# Emetteur2_2.net
KiCad netlist of a schematic drawn in EAGLE
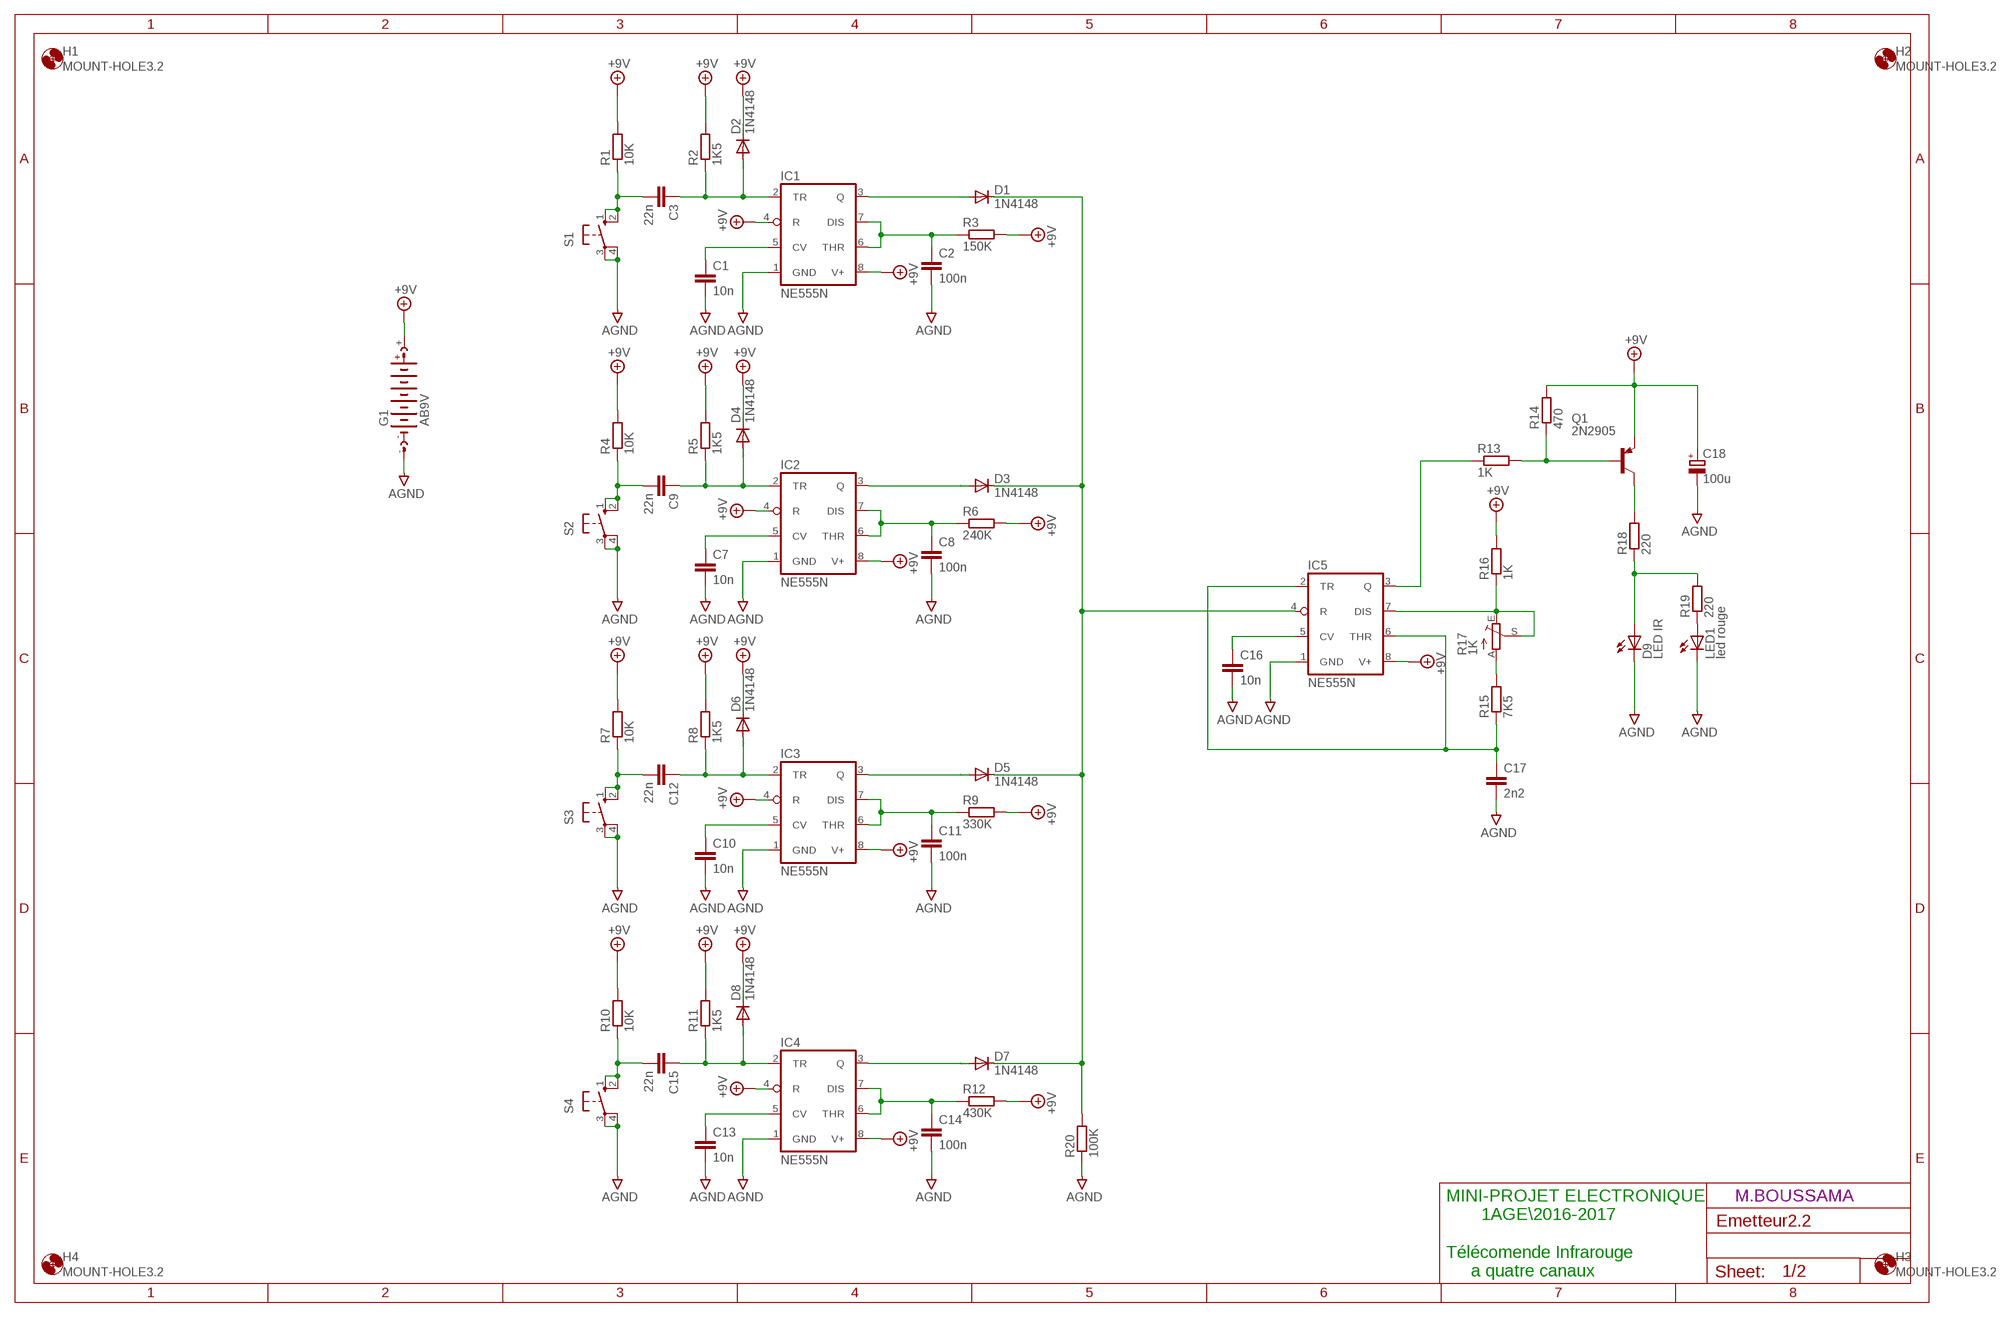
[diagram p0: schematic, sheet 1]
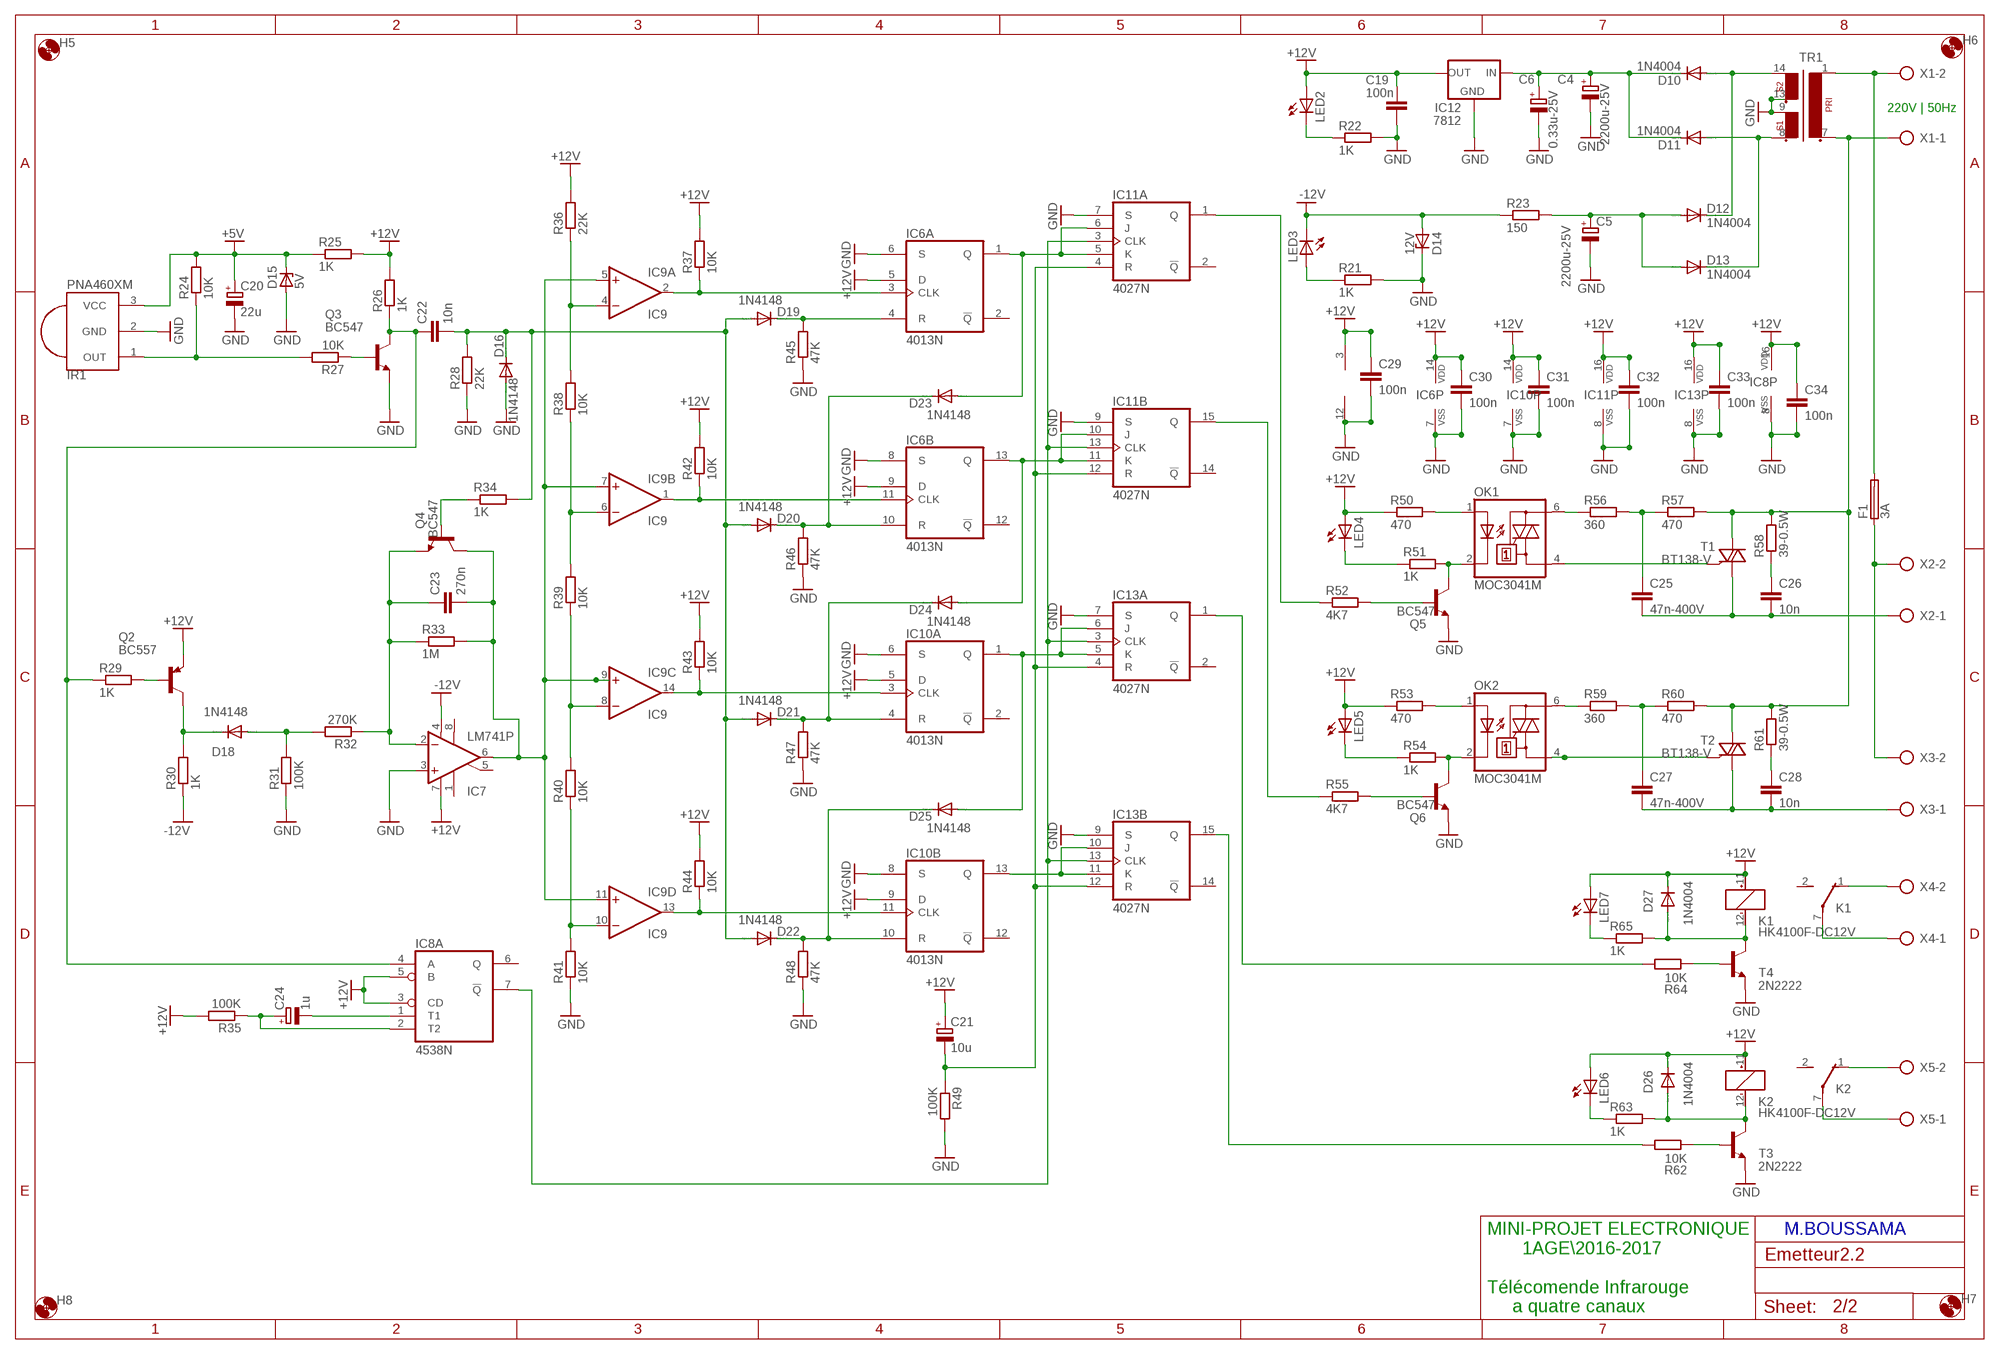
[diagram p1: schematic, sheet 2]

(export (version "E")
  (design (tool "Eeschema 10.0.6"))
  (components
    (comp (ref "C4")
      (value "2200u-25V")
      (footprint "eagle-import:E5-13")
      (libsource (lib "eagle-import") (part "CPOL-EUE5-13"))
    )
    (comp (ref "C5")
      (value "2200u-25V")
      (footprint "eagle-import:E5-13")
      (libsource (lib "eagle-import") (part "CPOL-EUE5-13"))
    )
    (comp (ref "C6")
      (value "0.33u-25V")
      (footprint "eagle-import:E5-5")
      (libsource (lib "eagle-import") (part "CPOL-EUE5-5"))
    )
    (comp (ref "C19")
      (value "100n")
      (footprint "eagle-import:C050-025X075")
      (libsource (lib "eagle-import") (part "C-EU050-025X075"))
    )
    (comp (ref "C20")
      (value "22u")
      (footprint "eagle-import:E2,5-6")
      (libsource (lib "eagle-import") (part "CPOL-EUE2.5-6"))
    )
    (comp (ref "C21")
      (value "10u")
      (footprint "eagle-import:E2,5-6E")
      (libsource (lib "eagle-import") (part "CPOL-EUE2,5-6E"))
    )
    (comp (ref "C22")
      (value "10n")
      (footprint "eagle-import:C050-025X075")
      (libsource (lib "eagle-import") (part "C-EU050-025X075"))
    )
    (comp (ref "C23")
      (value "270n")
      (footprint "eagle-import:C050-035X075")
      (libsource (lib "eagle-import") (part "C-EU050-035X075"))
    )
    (comp (ref "C24")
      (value "1u")
      (footprint "eagle-import:E2,5-6E")
      (libsource (lib "eagle-import") (part "CPOL-EUE2,5-6E"))
    )
    (comp (ref "C25")
      (value "47n-400V")
      (footprint "eagle-import:C150-054X183")
      (libsource (lib "eagle-import") (part "C-EU150-054X183"))
    )
    (comp (ref "C26")
      (value "10n")
      (footprint "eagle-import:C102-043X133")
      (libsource (lib "eagle-import") (part "C-EU102-043X133"))
    )
    (comp (ref "C27")
      (value "47n-400V")
      (footprint "eagle-import:C150-054X183")
      (libsource (lib "eagle-import") (part "C-EU150-054X183"))
    )
    (comp (ref "C28")
      (value "10n")
      (footprint "eagle-import:C102-043X133")
      (libsource (lib "eagle-import") (part "C-EU102-043X133"))
    )
    (comp (ref "C29")
      (value "100n")
      (footprint "eagle-import:C050-025X075")
      (libsource (lib "eagle-import") (part "C-EU050-025X075"))
    )
    (comp (ref "C30")
      (value "100n")
      (footprint "eagle-import:C050-025X075")
      (libsource (lib "eagle-import") (part "C-EU050-025X075"))
    )
    (comp (ref "C31")
      (value "100n")
      (footprint "eagle-import:C050-025X075")
      (libsource (lib "eagle-import") (part "C-EU050-025X075"))
    )
    (comp (ref "C32")
      (value "100n")
      (footprint "eagle-import:C050-025X075")
      (libsource (lib "eagle-import") (part "C-EU050-025X075"))
    )
    (comp (ref "C33")
      (value "100n")
      (footprint "eagle-import:C050-025X075")
      (libsource (lib "eagle-import") (part "C-EU050-025X075"))
    )
    (comp (ref "C34")
      (value "100n")
      (footprint "eagle-import:C050-025X075")
      (libsource (lib "eagle-import") (part "C-EU050-025X075"))
    )
    (comp (ref "D10")
      (value "1N4004")
      (footprint "eagle-import:DO41-10")
      (libsource (lib "eagle-import") (part "1N4004"))
    )
    (comp (ref "D11")
      (value "1N4004")
      (footprint "eagle-import:DO41-10")
      (libsource (lib "eagle-import") (part "1N4004"))
    )
    (comp (ref "D12")
      (value "1N4004")
      (footprint "eagle-import:DO41-10")
      (libsource (lib "eagle-import") (part "1N4004"))
    )
    (comp (ref "D13")
      (value "1N4004")
      (footprint "eagle-import:DO41-10")
      (libsource (lib "eagle-import") (part "1N4004"))
    )
    (comp (ref "D14")
      (value "12V")
      (footprint "eagle-import:DO41Z10")
      (libsource (lib "eagle-import") (part "1N4728"))
    )
    (comp (ref "D15")
      (value "5V")
      (footprint "eagle-import:DO41Z10")
      (libsource (lib "eagle-import") (part "1N4728"))
    )
    (comp (ref "D16")
      (value "1N4148")
      (footprint "eagle-import:DO35-10")
      (libsource (lib "eagle-import") (part "1N4148DO35-10"))
    )
    (comp (ref "D18")
      (value "1N4148")
      (footprint "eagle-import:DO35-7")
      (libsource (lib "eagle-import") (part "1N4148DO35-7"))
    )
    (comp (ref "D19")
      (value "1N4148")
      (footprint "eagle-import:DO35-10")
      (libsource (lib "eagle-import") (part "1N4148DO35-10"))
    )
    (comp (ref "D20")
      (value "1N4148")
      (footprint "eagle-import:SOD61B")
      (libsource (lib "eagle-import") (part "BY609"))
    )
    (comp (ref "D21")
      (value "1N4148")
      (footprint "eagle-import:DO35-10")
      (libsource (lib "eagle-import") (part "1N4148DO35-10"))
    )
    (comp (ref "D22")
      (value "1N4148")
      (footprint "eagle-import:SOD61B")
      (libsource (lib "eagle-import") (part "BY609"))
    )
    (comp (ref "D23")
      (value "1N4148")
      (footprint "eagle-import:DO35-10")
      (libsource (lib "eagle-import") (part "1N4148DO35-10"))
    )
    (comp (ref "D24")
      (value "1N4148")
      (footprint "eagle-import:SOD61B")
      (libsource (lib "eagle-import") (part "BY609"))
    )
    (comp (ref "D25")
      (value "1N4148")
      (footprint "eagle-import:DO35-10")
      (libsource (lib "eagle-import") (part "1N4148DO35-10"))
    )
    (comp (ref "D26")
      (value "1N4004")
      (footprint "eagle-import:DO41-10")
      (libsource (lib "eagle-import") (part "1N4004"))
    )
    (comp (ref "D27")
      (value "1N4004")
      (footprint "eagle-import:DO41-10")
      (libsource (lib "eagle-import") (part "1N4004"))
    )
    (comp (ref "F1")
      (value "3A")
      (footprint "eagle-import:GSH15")
      (libsource (lib "eagle-import") (part "FUSEGSH15"))
    )
    (comp (ref "H5")
      (value "MOUNT-HOLE3.2")
      (footprint "eagle-import:3,2")
      (libsource (lib "eagle-import") (part "MOUNT-HOLE3.2"))
    )
    (comp (ref "H6")
      (value "MOUNT-HOLE3.2")
      (footprint "eagle-import:3,2")
      (libsource (lib "eagle-import") (part "MOUNT-HOLE3.2"))
    )
    (comp (ref "H7")
      (value "MOUNT-HOLE3.2")
      (footprint "eagle-import:3,2")
      (libsource (lib "eagle-import") (part "MOUNT-HOLE3.2"))
    )
    (comp (ref "H8")
      (value "MOUNT-HOLE3.2")
      (footprint "eagle-import:3,2")
      (libsource (lib "eagle-import") (part "MOUNT-HOLE3.2"))
    )
    (comp (ref "IC6")
      (value "4013N")
      (footprint "eagle-import:DIL14")
      (libsource (lib "eagle-import") (part "4013N"))
    )
    (comp (ref "IC7")
      (value "LM741P")
      (footprint "eagle-import:DIL08")
      (libsource (lib "eagle-import") (part "741PLM"))
    )
    (comp (ref "IC8")
      (value "4538N")
      (footprint "eagle-import:DIL16")
      (libsource (lib "eagle-import") (part "4538N"))
    )
    (comp (ref "IC9")
      (value "IC9")
      (footprint "eagle-import:DIL14")
      (libsource (lib "eagle-import") (part "LM339N"))
    )
    (comp (ref "IC10")
      (value "4013N")
      (footprint "eagle-import:DIL14")
      (libsource (lib "eagle-import") (part "4013N"))
    )
    (comp (ref "IC11")
      (value "4027N")
      (footprint "eagle-import:DIL16")
      (libsource (lib "eagle-import") (part "4027N"))
    )
    (comp (ref "IC12")
      (value "7812")
      (footprint "eagle-import:78XXS")
      (libsource (lib "eagle-import") (part "78XXS"))
    )
    (comp (ref "IC13")
      (value "4027N")
      (footprint "eagle-import:DIL16")
      (libsource (lib "eagle-import") (part "4027N"))
    )
    (comp (ref "IR1")
      (value "PNA460XM")
      (footprint "eagle-import:PNA460XM")
      (libsource (lib "eagle-import") (part "PNA460XM"))
    )
    (comp (ref "K1")
      (value "HK4100F-DC12V")
      (footprint "eagle-import:SMR1")
      (libsource (lib "eagle-import") (part "HK410?F-0DC12V"))
    )
    (comp (ref "K2")
      (value "HK4100F-DC12V")
      (footprint "eagle-import:SMR1")
      (libsource (lib "eagle-import") (part "HK410?F-0DC12V"))
    )
    (comp (ref "LED2")
      (value "LED3MM")
      (footprint "eagle-import:LED3MM")
      (libsource (lib "eagle-import") (part "LED3MM"))
    )
    (comp (ref "LED3")
      (value "LED3MM")
      (footprint "eagle-import:LED3MM")
      (libsource (lib "eagle-import") (part "LED3MM"))
    )
    (comp (ref "LED4")
      (value "LED3MM")
      (footprint "eagle-import:LED3MM")
      (libsource (lib "eagle-import") (part "LED3MM"))
    )
    (comp (ref "LED5")
      (value "LED3MM")
      (footprint "eagle-import:LED3MM")
      (libsource (lib "eagle-import") (part "LED3MM"))
    )
    (comp (ref "LED6")
      (value "LED3MM")
      (footprint "eagle-import:LED3MM")
      (libsource (lib "eagle-import") (part "LED3MM"))
    )
    (comp (ref "LED7")
      (value "LED3MM")
      (footprint "eagle-import:LED3MM")
      (libsource (lib "eagle-import") (part "LED3MM"))
    )
    (comp (ref "OK1")
      (value "MOC3041M")
      (footprint "eagle-import:DIL06")
      (fields (field (name "MF") "FAIRCHILD SEMICONDUCTOR"))
      (libsource (lib "eagle-import") (part "MOC3041M"))
    )
    (comp (ref "OK2")
      (value "MOC3041M")
      (footprint "eagle-import:DIL06")
      (fields (field (name "MF") "FAIRCHILD SEMICONDUCTOR"))
      (libsource (lib "eagle-import") (part "MOC3041M"))
    )
    (comp (ref "Q2")
      (value "BC557")
      (footprint "eagle-import:TO92-EBC")
      (libsource (lib "eagle-import") (part "BC557"))
    )
    (comp (ref "Q3")
      (value "BC547")
      (footprint "eagle-import:TO92-EBC")
      (libsource (lib "eagle-import") (part "BC548"))
    )
    (comp (ref "Q4")
      (value "BC547")
      (footprint "eagle-import:TO92-EBC")
      (libsource (lib "eagle-import") (part "BC548"))
    )
    (comp (ref "Q5")
      (value "BC547")
      (footprint "eagle-import:TO92-EBC")
      (libsource (lib "eagle-import") (part "BC548"))
    )
    (comp (ref "Q6")
      (value "BC547")
      (footprint "eagle-import:TO92-EBC")
      (libsource (lib "eagle-import") (part "BC548"))
    )
    (comp (ref "R21")
      (value "1K")
      (footprint "eagle-import:0207_10")
      (libsource (lib "eagle-import") (part "R-EU_0207/10"))
    )
    (comp (ref "R22")
      (value "1K")
      (footprint "eagle-import:0207_10")
      (libsource (lib "eagle-import") (part "R-EU_0207/10"))
    )
    (comp (ref "R23")
      (value "150")
      (footprint "eagle-import:0207_10")
      (libsource (lib "eagle-import") (part "R-EU_0207/10"))
    )
    (comp (ref "R24")
      (value "10K")
      (footprint "eagle-import:0207_10")
      (libsource (lib "eagle-import") (part "R-EU_0207/10"))
    )
    (comp (ref "R25")
      (value "1K")
      (footprint "eagle-import:0207_10")
      (libsource (lib "eagle-import") (part "R-EU_0207/10"))
    )
    (comp (ref "R26")
      (value "1K")
      (footprint "eagle-import:0207_12")
      (libsource (lib "eagle-import") (part "R-EU_0207/12"))
    )
    (comp (ref "R27")
      (value "10K")
      (footprint "eagle-import:0207_10")
      (libsource (lib "eagle-import") (part "R-EU_0207/10"))
    )
    (comp (ref "R28")
      (value "22K")
      (footprint "eagle-import:0207_10")
      (libsource (lib "eagle-import") (part "R-EU_0207/10"))
    )
    (comp (ref "R29")
      (value "1K")
      (footprint "eagle-import:0207_15")
      (libsource (lib "eagle-import") (part "R-EU_0207/15"))
    )
    (comp (ref "R30")
      (value "1K")
      (footprint "eagle-import:0207_10")
      (libsource (lib "eagle-import") (part "R-EU_0207/10"))
    )
    (comp (ref "R31")
      (value "100K")
      (footprint "eagle-import:0207_10")
      (libsource (lib "eagle-import") (part "R-EU_0207/10"))
    )
    (comp (ref "R32")
      (value "270K")
      (footprint "eagle-import:0207_12")
      (libsource (lib "eagle-import") (part "R-EU_0207/12"))
    )
    (comp (ref "R33")
      (value "1M")
      (footprint "eagle-import:0207_10")
      (libsource (lib "eagle-import") (part "R-EU_0207/10"))
    )
    (comp (ref "R34")
      (value "1K")
      (footprint "eagle-import:0207_12")
      (libsource (lib "eagle-import") (part "R-EU_0207/12"))
    )
    (comp (ref "R35")
      (value "100K")
      (footprint "eagle-import:0207_10")
      (libsource (lib "eagle-import") (part "R-EU_0207/10"))
    )
    (comp (ref "R36")
      (value "22K")
      (footprint "eagle-import:0207_10")
      (libsource (lib "eagle-import") (part "R-EU_0207/10"))
    )
    (comp (ref "R37")
      (value "10K")
      (footprint "eagle-import:0207_10")
      (libsource (lib "eagle-import") (part "R-EU_0207/10"))
    )
    (comp (ref "R38")
      (value "10K")
      (footprint "eagle-import:0207_10")
      (libsource (lib "eagle-import") (part "R-EU_0207/10"))
    )
    (comp (ref "R39")
      (value "10K")
      (footprint "eagle-import:0207_10")
      (libsource (lib "eagle-import") (part "R-EU_0207/10"))
    )
    (comp (ref "R40")
      (value "10K")
      (footprint "eagle-import:0207_10")
      (libsource (lib "eagle-import") (part "R-EU_0207/10"))
    )
    (comp (ref "R41")
      (value "10K")
      (footprint "eagle-import:0207_10")
      (libsource (lib "eagle-import") (part "R-EU_0207/10"))
    )
    (comp (ref "R42")
      (value "10K")
      (footprint "eagle-import:0207_10")
      (libsource (lib "eagle-import") (part "R-EU_0207/10"))
    )
    (comp (ref "R43")
      (value "10K")
      (footprint "eagle-import:0207_10")
      (libsource (lib "eagle-import") (part "R-EU_0207/10"))
    )
    (comp (ref "R44")
      (value "10K")
      (footprint "eagle-import:0207_10")
      (libsource (lib "eagle-import") (part "R-EU_0207/10"))
    )
    (comp (ref "R45")
      (value "47K")
      (footprint "eagle-import:0207_12")
      (libsource (lib "eagle-import") (part "R-EU_0207/12"))
    )
    (comp (ref "R46")
      (value "47K")
      (footprint "eagle-import:0207_12")
      (libsource (lib "eagle-import") (part "R-EU_0207/12"))
    )
    (comp (ref "R47")
      (value "47K")
      (footprint "eagle-import:0207_12")
      (libsource (lib "eagle-import") (part "R-EU_0207/12"))
    )
    (comp (ref "R48")
      (value "47K")
      (footprint "eagle-import:0207_10")
      (libsource (lib "eagle-import") (part "R-EU_0207/10"))
    )
    (comp (ref "R49")
      (value "100K")
      (footprint "eagle-import:0207_12")
      (libsource (lib "eagle-import") (part "R-EU_0207/12"))
    )
    (comp (ref "R50")
      (value "470")
      (footprint "eagle-import:0207_10")
      (libsource (lib "eagle-import") (part "R-EU_0207/10"))
    )
    (comp (ref "R51")
      (value "1K")
      (footprint "eagle-import:0207_10")
      (libsource (lib "eagle-import") (part "R-EU_0207/10"))
    )
    (comp (ref "R52")
      (value "4K7")
      (footprint "eagle-import:0207_10")
      (libsource (lib "eagle-import") (part "R-EU_0207/10"))
    )
    (comp (ref "R53")
      (value "470")
      (footprint "eagle-import:0207_10")
      (libsource (lib "eagle-import") (part "R-EU_0207/10"))
    )
    (comp (ref "R54")
      (value "1K")
      (footprint "eagle-import:0207_10")
      (libsource (lib "eagle-import") (part "R-EU_0207/10"))
    )
    (comp (ref "R55")
      (value "4K7")
      (footprint "eagle-import:0207_10")
      (libsource (lib "eagle-import") (part "R-EU_0207/10"))
    )
    (comp (ref "R56")
      (value "360")
      (footprint "eagle-import:0207_10")
      (libsource (lib "eagle-import") (part "R-EU_0207/10"))
    )
    (comp (ref "R57")
      (value "470")
      (footprint "eagle-import:0207_10")
      (libsource (lib "eagle-import") (part "R-EU_0207/10"))
    )
    (comp (ref "R58")
      (value "39-0.5W")
      (footprint "eagle-import:0207_10")
      (libsource (lib "eagle-import") (part "R-EU_0207/10"))
    )
    (comp (ref "R59")
      (value "360")
      (footprint "eagle-import:0207_10")
      (libsource (lib "eagle-import") (part "R-EU_0207/10"))
    )
    (comp (ref "R60")
      (value "470")
      (footprint "eagle-import:0207_10")
      (libsource (lib "eagle-import") (part "R-EU_0207/10"))
    )
    (comp (ref "R61")
      (value "39-0.5W")
      (footprint "eagle-import:0207_10")
      (libsource (lib "eagle-import") (part "R-EU_0207/10"))
    )
    (comp (ref "R62")
      (value "10K")
      (footprint "eagle-import:0207_12")
      (libsource (lib "eagle-import") (part "R-EU_0207/12"))
    )
    (comp (ref "R63")
      (value "1K")
      (footprint "eagle-import:0207_10")
      (libsource (lib "eagle-import") (part "R-EU_0207/10"))
    )
    (comp (ref "R64")
      (value "10K")
      (footprint "eagle-import:0207_12")
      (libsource (lib "eagle-import") (part "R-EU_0207/12"))
    )
    (comp (ref "R65")
      (value "1K")
      (footprint "eagle-import:0207_10")
      (libsource (lib "eagle-import") (part "R-EU_0207/10"))
    )
    (comp (ref "T1")
      (value "BT138-V")
      (footprint "eagle-import:TO220BV")
      (libsource (lib "eagle-import") (part "BT138-V"))
    )
    (comp (ref "T2")
      (value "BT138-V")
      (footprint "eagle-import:TO220BV")
      (libsource (lib "eagle-import") (part "BT138-V"))
    )
    (comp (ref "T3")
      (value "2N2222")
      (footprint "eagle-import:TO92-EBC-OVAL")
      (libsource (lib "eagle-import") (part "2N2222"))
    )
    (comp (ref "T4")
      (value "2N2222")
      (footprint "eagle-import:TO92-EBC-OVAL")
      (libsource (lib "eagle-import") (part "2N2222"))
    )
    (comp (ref "TR1")
      (value "EI54-2")
      (footprint "eagle-import:EI54-2")
      (libsource (lib "eagle-import") (part "EI54-2"))
    )
    (comp (ref "X1")
      (value "AK300/2")
      (footprint "eagle-import:AK300_2")
      (libsource (lib "eagle-import") (part "AK300/2"))
    )
    (comp (ref "X2")
      (value "AK300/2")
      (footprint "eagle-import:AK300_2")
      (libsource (lib "eagle-import") (part "AK300/2"))
    )
    (comp (ref "X3")
      (value "AK300/2")
      (footprint "eagle-import:AK300_2")
      (libsource (lib "eagle-import") (part "AK300/2"))
    )
    (comp (ref "X4")
      (value "AK300/2")
      (footprint "eagle-import:AK300_2")
      (libsource (lib "eagle-import") (part "AK300/2"))
    )
    (comp (ref "X5")
      (value "AK300/2")
      (footprint "eagle-import:AK300_2")
      (libsource (lib "eagle-import") (part "AK300/2"))
    )
    (comp (ref "C1")
      (value "10n")
      (footprint "eagle-import:C050-025X075")
      (libsource (lib "eagle-import") (part "C-EU050-025X075"))
    )
    (comp (ref "C2")
      (value "100n")
      (footprint "eagle-import:C050-030X075")
      (libsource (lib "eagle-import") (part "C-EU050-030X075"))
    )
    (comp (ref "C3")
      (value "22n")
      (footprint "eagle-import:C050-025X075")
      (libsource (lib "eagle-import") (part "C-EU050-025X075"))
    )
    (comp (ref "C7")
      (value "10n")
      (footprint "eagle-import:C050-025X075")
      (libsource (lib "eagle-import") (part "C-EU050-025X075"))
    )
    (comp (ref "C8")
      (value "100n")
      (footprint "eagle-import:C050-030X075")
      (libsource (lib "eagle-import") (part "C-EU050-030X075"))
    )
    (comp (ref "C9")
      (value "22n")
      (footprint "eagle-import:C050-025X075")
      (libsource (lib "eagle-import") (part "C-EU050-025X075"))
    )
    (comp (ref "C10")
      (value "10n")
      (footprint "eagle-import:C050-025X075")
      (libsource (lib "eagle-import") (part "C-EU050-025X075"))
    )
    (comp (ref "C11")
      (value "100n")
      (footprint "eagle-import:C050-030X075")
      (libsource (lib "eagle-import") (part "C-EU050-030X075"))
    )
    (comp (ref "C12")
      (value "22n")
      (footprint "eagle-import:C050-025X075")
      (libsource (lib "eagle-import") (part "C-EU050-025X075"))
    )
    (comp (ref "C13")
      (value "10n")
      (footprint "eagle-import:C050-025X075")
      (libsource (lib "eagle-import") (part "C-EU050-025X075"))
    )
    (comp (ref "C14")
      (value "100n")
      (footprint "eagle-import:C050-030X075")
      (libsource (lib "eagle-import") (part "C-EU050-030X075"))
    )
    (comp (ref "C15")
      (value "22n")
      (footprint "eagle-import:C050-025X075")
      (libsource (lib "eagle-import") (part "C-EU050-025X075"))
    )
    (comp (ref "C16")
      (value "10n")
      (footprint "eagle-import:C050-025X075")
      (libsource (lib "eagle-import") (part "C-EU050-025X075"))
    )
    (comp (ref "C17")
      (value "2n2")
      (footprint "eagle-import:C050-025X075")
      (libsource (lib "eagle-import") (part "C-EU050-025X075"))
    )
    (comp (ref "C18")
      (value "100u")
      (footprint "eagle-import:E5-4")
      (libsource (lib "eagle-import") (part "CPOL-EUE5-4"))
    )
    (comp (ref "D1")
      (value "1N4148")
      (footprint "eagle-import:DO35-7")
      (libsource (lib "eagle-import") (part "1N4148DO35-7"))
    )
    (comp (ref "D2")
      (value "1N4148")
      (footprint "eagle-import:DO35-7")
      (libsource (lib "eagle-import") (part "1N4148DO35-7"))
    )
    (comp (ref "D3")
      (value "1N4148")
      (footprint "eagle-import:DO35-7")
      (libsource (lib "eagle-import") (part "1N4148DO35-7"))
    )
    (comp (ref "D4")
      (value "1N4148")
      (footprint "eagle-import:DO35-7")
      (libsource (lib "eagle-import") (part "1N4148DO35-7"))
    )
    (comp (ref "D5")
      (value "1N4148")
      (footprint "eagle-import:DO35-7")
      (libsource (lib "eagle-import") (part "1N4148DO35-7"))
    )
    (comp (ref "D6")
      (value "1N4148")
      (footprint "eagle-import:DO35-7")
      (libsource (lib "eagle-import") (part "1N4148DO35-7"))
    )
    (comp (ref "D7")
      (value "1N4148")
      (footprint "eagle-import:DO35-7")
      (libsource (lib "eagle-import") (part "1N4148DO35-7"))
    )
    (comp (ref "D8")
      (value "1N4148")
      (footprint "eagle-import:DO35-7")
      (libsource (lib "eagle-import") (part "1N4148DO35-7"))
    )
    (comp (ref "D9")
      (value "LED IR")
      (footprint "eagle-import:SFH482")
      (libsource (lib "eagle-import") (part "SFH482"))
    )
    (comp (ref "G1")
      (value "AB9V")
      (footprint "eagle-import:AB9V")
      (libsource (lib "eagle-import") (part "AB9V"))
    )
    (comp (ref "H1")
      (value "MOUNT-HOLE3.2")
      (footprint "eagle-import:3,2")
      (libsource (lib "eagle-import") (part "MOUNT-HOLE3.2"))
    )
    (comp (ref "H2")
      (value "MOUNT-HOLE3.2")
      (footprint "eagle-import:3,2")
      (libsource (lib "eagle-import") (part "MOUNT-HOLE3.2"))
    )
    (comp (ref "H3")
      (value "MOUNT-HOLE3.2")
      (footprint "eagle-import:3,2")
      (libsource (lib "eagle-import") (part "MOUNT-HOLE3.2"))
    )
    (comp (ref "H4")
      (value "MOUNT-HOLE3.2")
      (footprint "eagle-import:3,2")
      (libsource (lib "eagle-import") (part "MOUNT-HOLE3.2"))
    )
    (comp (ref "IC1")
      (value "NE555N")
      (footprint "eagle-import:DIL08")
      (libsource (lib "eagle-import") (part "555NNE"))
    )
    (comp (ref "IC2")
      (value "NE555N")
      (footprint "eagle-import:DIL08")
      (libsource (lib "eagle-import") (part "555NNE"))
    )
    (comp (ref "IC3")
      (value "NE555N")
      (footprint "eagle-import:DIL08")
      (libsource (lib "eagle-import") (part "555NNE"))
    )
    (comp (ref "IC4")
      (value "NE555N")
      (footprint "eagle-import:DIL08")
      (libsource (lib "eagle-import") (part "555NNE"))
    )
    (comp (ref "IC5")
      (value "NE555N")
      (footprint "eagle-import:DIL08")
      (libsource (lib "eagle-import") (part "555NNE"))
    )
    (comp (ref "LED1")
      (value "led rouge")
      (footprint "eagle-import:LED3MM")
      (libsource (lib "eagle-import") (part "LED3MM"))
    )
    (comp (ref "Q1")
      (value "2N2905")
      (footprint "eagle-import:TO5")
      (libsource (lib "eagle-import") (part "2N2905"))
    )
    (comp (ref "R1")
      (value "10K")
      (footprint "eagle-import:0207_12")
      (libsource (lib "eagle-import") (part "R-EU_0207/12"))
    )
    (comp (ref "R2")
      (value "1K5")
      (footprint "eagle-import:0207_10")
      (libsource (lib "eagle-import") (part "R-EU_0207/10"))
    )
    (comp (ref "R3")
      (value "150K")
      (footprint "eagle-import:0204_7")
      (libsource (lib "eagle-import") (part "R-EU_0204/7"))
    )
    (comp (ref "R4")
      (value "10K")
      (footprint "eagle-import:0207_12")
      (libsource (lib "eagle-import") (part "R-EU_0207/12"))
    )
    (comp (ref "R5")
      (value "1K5")
      (footprint "eagle-import:0207_10")
      (libsource (lib "eagle-import") (part "R-EU_0207/10"))
    )
    (comp (ref "R6")
      (value "240K")
      (footprint "eagle-import:0204_7")
      (libsource (lib "eagle-import") (part "R-EU_0204/7"))
    )
    (comp (ref "R7")
      (value "10K")
      (footprint "eagle-import:0207_12")
      (libsource (lib "eagle-import") (part "R-EU_0207/12"))
    )
    (comp (ref "R8")
      (value "1K5")
      (footprint "eagle-import:0207_10")
      (libsource (lib "eagle-import") (part "R-EU_0207/10"))
    )
    (comp (ref "R9")
      (value "330K")
      (footprint "eagle-import:0204_7")
      (libsource (lib "eagle-import") (part "R-EU_0204/7"))
    )
    (comp (ref "R10")
      (value "10K")
      (footprint "eagle-import:0207_12")
      (libsource (lib "eagle-import") (part "R-EU_0207/12"))
    )
    (comp (ref "R11")
      (value "1K5")
      (footprint "eagle-import:0207_10")
      (libsource (lib "eagle-import") (part "R-EU_0207/10"))
    )
    (comp (ref "R12")
      (value "430K")
      (footprint "eagle-import:0204_7")
      (libsource (lib "eagle-import") (part "R-EU_0204/7"))
    )
    (comp (ref "R13")
      (value "1K")
      (footprint "eagle-import:0207_12")
      (libsource (lib "eagle-import") (part "R-EU_0207/12"))
    )
    (comp (ref "R14")
      (value "470")
      (footprint "eagle-import:0207_10")
      (libsource (lib "eagle-import") (part "R-EU_0207/10"))
    )
    (comp (ref "R15")
      (value "7K5")
      (footprint "eagle-import:0207_10")
      (libsource (lib "eagle-import") (part "R-EU_0207/10"))
    )
    (comp (ref "R16")
      (value "1K")
      (footprint "eagle-import:0207_12")
      (libsource (lib "eagle-import") (part "R-EU_0207/12"))
    )
    (comp (ref "R17")
      (value "1K")
      (footprint "eagle-import:B25P")
      (libsource (lib "eagle-import") (part "TRIM_EU-B25P"))
    )
    (comp (ref "R18")
      (value "220")
      (footprint "eagle-import:0207_10")
      (libsource (lib "eagle-import") (part "R-EU_0207/10"))
    )
    (comp (ref "R19")
      (value "220")
      (footprint "eagle-import:0207_10")
      (libsource (lib "eagle-import") (part "R-EU_0207/10"))
    )
    (comp (ref "R20")
      (value "100K")
      (footprint "eagle-import:0207_10")
      (libsource (lib "eagle-import") (part "R-EU_0207/10"))
    )
    (comp (ref "S1")
      (value "10-XX")
      (footprint "eagle-import:B3F-10XX")
      (fields (field (name "MPN") "B3F-1000"))
      (libsource (lib "eagle-import") (part "10-XX"))
    )
    (comp (ref "S2")
      (value "10-XX")
      (footprint "eagle-import:B3F-10XX")
      (fields (field (name "MPN") "B3F-1000"))
      (libsource (lib "eagle-import") (part "10-XX"))
    )
    (comp (ref "S3")
      (value "10-XX")
      (footprint "eagle-import:B3F-10XX")
      (fields (field (name "MPN") "B3F-1000"))
      (libsource (lib "eagle-import") (part "10-XX"))
    )
    (comp (ref "S4")
      (value "10-XX")
      (footprint "eagle-import:B3F-10XX")
      (fields (field (name "MPN") "B3F-1000"))
      (libsource (lib "eagle-import") (part "10-XX"))
    )
  )
  (nets
    (net (code "1") (name "+5V") (class "Default")
      (node (ref "C20") (pin "+") (pinfunction "+_+") (pintype "passive"))
      (node (ref "D15") (pin "C") (pinfunction "C_C") (pintype "passive"))
      (node (ref "IR1") (pin "3") (pinfunction "VCC_3") (pintype "power_in"))
      (node (ref "R24") (pin "2") (pinfunction "2_2") (pintype "passive"))
      (node (ref "R25") (pin "1") (pinfunction "1_1") (pintype "passive"))
    )
    (net (code "2") (name "+9V") (class "Default")
      (node (ref "C18") (pin "+") (pinfunction "+_+") (pintype "passive"))
      (node (ref "D2") (pin "C") (pinfunction "C_C") (pintype "passive"))
      (node (ref "D4") (pin "C") (pinfunction "C_C") (pintype "passive"))
      (node (ref "D6") (pin "C") (pinfunction "C_C") (pintype "passive"))
      (node (ref "D8") (pin "C") (pinfunction "C_C") (pintype "passive"))
      (node (ref "G1") (pin "+") (pinfunction "+_+") (pintype "passive"))
      (node (ref "IC1") (pin "4") (pinfunction "R_4") (pintype "input"))
      (node (ref "IC1") (pin "8") (pinfunction "V+_8") (pintype "power_in"))
      (node (ref "IC2") (pin "4") (pinfunction "R_4") (pintype "input"))
      (node (ref "IC2") (pin "8") (pinfunction "V+_8") (pintype "power_in"))
      (node (ref "IC3") (pin "4") (pinfunction "R_4") (pintype "input"))
      (node (ref "IC3") (pin "8") (pinfunction "V+_8") (pintype "power_in"))
      (node (ref "IC4") (pin "4") (pinfunction "R_4") (pintype "input"))
      (node (ref "IC4") (pin "8") (pinfunction "V+_8") (pintype "power_in"))
      (node (ref "IC5") (pin "8") (pinfunction "V+_8") (pintype "power_in"))
      (node (ref "Q1") (pin "1") (pinfunction "E_1") (pintype "passive"))
      (node (ref "R1") (pin "2") (pinfunction "2_2") (pintype "passive"))
      (node (ref "R10") (pin "2") (pinfunction "2_2") (pintype "passive"))
      (node (ref "R11") (pin "2") (pinfunction "2_2") (pintype "passive"))
      (node (ref "R12") (pin "2") (pinfunction "2_2") (pintype "passive"))
      (node (ref "R14") (pin "2") (pinfunction "2_2") (pintype "passive"))
      (node (ref "R16") (pin "2") (pinfunction "2_2") (pintype "passive"))
      (node (ref "R2") (pin "2") (pinfunction "2_2") (pintype "passive"))
      (node (ref "R3") (pin "2") (pinfunction "2_2") (pintype "passive"))
      (node (ref "R4") (pin "2") (pinfunction "2_2") (pintype "passive"))
      (node (ref "R5") (pin "2") (pinfunction "2_2") (pintype "passive"))
      (node (ref "R6") (pin "2") (pinfunction "2_2") (pintype "passive"))
      (node (ref "R7") (pin "2") (pinfunction "2_2") (pintype "passive"))
      (node (ref "R8") (pin "2") (pinfunction "2_2") (pintype "passive"))
      (node (ref "R9") (pin "2") (pinfunction "2_2") (pintype "passive"))
    )
    (net (code "3") (name "+12V") (class "Default")
      (node (ref "C19") (pin "1") (pinfunction "1_1") (pintype "passive"))
      (node (ref "C21") (pin "+") (pinfunction "+_+") (pintype "passive"))
      (node (ref "C29") (pin "1") (pinfunction "1_1") (pintype "passive"))
      (node (ref "C30") (pin "1") (pinfunction "1_1") (pintype "passive"))
      (node (ref "C31") (pin "1") (pinfunction "1_1") (pintype "passive"))
      (node (ref "C32") (pin "1") (pinfunction "1_1") (pintype "passive"))
      (node (ref "C33") (pin "1") (pinfunction "1_1") (pintype "passive"))
      (node (ref "C34") (pin "1") (pinfunction "1_1") (pintype "passive"))
      (node (ref "D26") (pin "C") (pinfunction "C_C") (pintype "passive"))
      (node (ref "D27") (pin "C") (pinfunction "C_C") (pintype "passive"))
      (node (ref "IC10") (pin "14") (pinfunction "VDD_14") (pintype "power_in"))
      (node (ref "IC10") (pin "5") (pinfunction "D_5") (pintype "input"))
      (node (ref "IC10") (pin "9") (pinfunction "D_9") (pintype "input"))
      (node (ref "IC11") (pin "16") (pinfunction "VDD_16") (pintype "power_in"))
      (node (ref "IC12") (pin "OUT") (pinfunction "OUT_OUT") (pintype "passive"))
      (node (ref "IC13") (pin "16") (pinfunction "VDD_16") (pintype "power_in"))
      (node (ref "IC6") (pin "14") (pinfunction "VDD_14") (pintype "power_in"))
      (node (ref "IC6") (pin "5") (pinfunction "D_5") (pintype "input"))
      (node (ref "IC6") (pin "9") (pinfunction "D_9") (pintype "input"))
      (node (ref "IC7") (pin "7") (pinfunction "V+_7") (pintype "power_in"))
      (node (ref "IC8") (pin "16") (pinfunction "VDD_16") (pintype "power_in"))
      (node (ref "IC8") (pin "3") (pinfunction "CD_3") (pintype "input"))
      (node (ref "IC8") (pin "5") (pinfunction "B_5") (pintype "input"))
      (node (ref "IC9") (pin "3") (pinfunction "V+_3") (pintype "power_in"))
      (node (ref "K1") (pin "11") (pinfunction "+_11") (pintype "passive"))
      (node (ref "K2") (pin "11") (pinfunction "+_11") (pintype "passive"))
      (node (ref "LED2") (pin "A") (pinfunction "A_A") (pintype "passive"))
      (node (ref "LED4") (pin "A") (pinfunction "A_A") (pintype "passive"))
      (node (ref "LED5") (pin "A") (pinfunction "A_A") (pintype "passive"))
      (node (ref "LED6") (pin "A") (pinfunction "A_A") (pintype "passive"))
      (node (ref "LED7") (pin "A") (pinfunction "A_A") (pintype "passive"))
      (node (ref "Q2") (pin "E") (pinfunction "E_E") (pintype "passive"))
      (node (ref "R25") (pin "2") (pinfunction "2_2") (pintype "passive"))
      (node (ref "R26") (pin "2") (pinfunction "2_2") (pintype "passive"))
      (node (ref "R35") (pin "2") (pinfunction "2_2") (pintype "passive"))
      (node (ref "R36") (pin "2") (pinfunction "2_2") (pintype "passive"))
      (node (ref "R37") (pin "2") (pinfunction "2_2") (pintype "passive"))
      (node (ref "R42") (pin "2") (pinfunction "2_2") (pintype "passive"))
      (node (ref "R43") (pin "2") (pinfunction "2_2") (pintype "passive"))
      (node (ref "R44") (pin "2") (pinfunction "2_2") (pintype "passive"))
      (node (ref "R50") (pin "1") (pinfunction "1_1") (pintype "passive"))
      (node (ref "R53") (pin "1") (pinfunction "1_1") (pintype "passive"))
    )
    (net (code "4") (name "-12V") (class "Default")
      (node (ref "D14") (pin "A") (pinfunction "A_A") (pintype "passive"))
      (node (ref "IC7") (pin "4") (pinfunction "V-_4") (pintype "power_in"))
      (node (ref "LED3") (pin "K") (pinfunction "C_K") (pintype "passive"))
      (node (ref "R23") (pin "1") (pinfunction "1_1") (pintype "passive"))
      (node (ref "R30") (pin "1") (pinfunction "1_1") (pintype "passive"))
    )
    (net (code "5") (name "AGND") (class "Default")
      (node (ref "C1") (pin "2") (pinfunction "2_2") (pintype "passive"))
      (node (ref "C10") (pin "2") (pinfunction "2_2") (pintype "passive"))
      (node (ref "C11") (pin "2") (pinfunction "2_2") (pintype "passive"))
      (node (ref "C13") (pin "2") (pinfunction "2_2") (pintype "passive"))
      (node (ref "C14") (pin "2") (pinfunction "2_2") (pintype "passive"))
      (node (ref "C16") (pin "2") (pinfunction "2_2") (pintype "passive"))
      (node (ref "C17") (pin "2") (pinfunction "2_2") (pintype "passive"))
      (node (ref "C18") (pin "-") (pinfunction "-_-") (pintype "passive"))
      (node (ref "C2") (pin "2") (pinfunction "2_2") (pintype "passive"))
      (node (ref "C7") (pin "2") (pinfunction "2_2") (pintype "passive"))
      (node (ref "C8") (pin "2") (pinfunction "2_2") (pintype "passive"))
      (node (ref "D9") (pin "K") (pinfunction "C_K") (pintype "passive"))
      (node (ref "G1") (pin "-") (pinfunction "-_-") (pintype "passive"))
      (node (ref "IC1") (pin "1") (pinfunction "GND_1") (pintype "power_in"))
      (node (ref "IC2") (pin "1") (pinfunction "GND_1") (pintype "power_in"))
      (node (ref "IC3") (pin "1") (pinfunction "GND_1") (pintype "power_in"))
      (node (ref "IC4") (pin "1") (pinfunction "GND_1") (pintype "power_in"))
      (node (ref "IC5") (pin "1") (pinfunction "GND_1") (pintype "power_in"))
      (node (ref "LED1") (pin "K") (pinfunction "C_K") (pintype "passive"))
      (node (ref "R20") (pin "1") (pinfunction "1_1") (pintype "passive"))
      (node (ref "S1") (pin "3") (pinfunction "P_3") (pintype "passive"))
      (node (ref "S1") (pin "4") (pinfunction "P1_4") (pintype "passive"))
      (node (ref "S2") (pin "3") (pinfunction "P_3") (pintype "passive"))
      (node (ref "S2") (pin "4") (pinfunction "P1_4") (pintype "passive"))
      (node (ref "S3") (pin "3") (pinfunction "P_3") (pintype "passive"))
      (node (ref "S3") (pin "4") (pinfunction "P1_4") (pintype "passive"))
      (node (ref "S4") (pin "3") (pinfunction "P_3") (pintype "passive"))
      (node (ref "S4") (pin "4") (pinfunction "P1_4") (pintype "passive"))
    )
    (net (code "6") (name "GND") (class "Default")
      (node (ref "C19") (pin "2") (pinfunction "2_2") (pintype "passive"))
      (node (ref "C20") (pin "-") (pinfunction "-_-") (pintype "passive"))
      (node (ref "C29") (pin "2") (pinfunction "2_2") (pintype "passive"))
      (node (ref "C30") (pin "2") (pinfunction "2_2") (pintype "passive"))
      (node (ref "C31") (pin "2") (pinfunction "2_2") (pintype "passive"))
      (node (ref "C32") (pin "2") (pinfunction "2_2") (pintype "passive"))
      (node (ref "C33") (pin "2") (pinfunction "2_2") (pintype "passive"))
      (node (ref "C34") (pin "2") (pinfunction "2_2") (pintype "passive"))
      (node (ref "C4") (pin "-") (pinfunction "-_-") (pintype "passive"))
      (node (ref "C5") (pin "-") (pinfunction "-_-") (pintype "passive"))
      (node (ref "C6") (pin "-") (pinfunction "-_-") (pintype "passive"))
      (node (ref "D14") (pin "C") (pinfunction "C_C") (pintype "passive"))
      (node (ref "D15") (pin "A") (pinfunction "A_A") (pintype "passive"))
      (node (ref "D16") (pin "A") (pinfunction "A_A") (pintype "passive"))
      (node (ref "IC10") (pin "6") (pinfunction "S_6") (pintype "input"))
      (node (ref "IC10") (pin "7") (pinfunction "VSS_7") (pintype "power_in"))
      (node (ref "IC10") (pin "8") (pinfunction "S_8") (pintype "input"))
      (node (ref "IC11") (pin "7") (pinfunction "S_7") (pintype "input"))
      (node (ref "IC11") (pin "8") (pinfunction "VSS_8") (pintype "power_in"))
      (node (ref "IC11") (pin "9") (pinfunction "S_9") (pintype "input"))
      (node (ref "IC12") (pin "GND") (pinfunction "GND_GND") (pintype "input"))
      (node (ref "IC13") (pin "7") (pinfunction "S_7") (pintype "input"))
      (node (ref "IC13") (pin "8") (pinfunction "VSS_8") (pintype "power_in"))
      (node (ref "IC13") (pin "9") (pinfunction "S_9") (pintype "input"))
      (node (ref "IC6") (pin "6") (pinfunction "S_6") (pintype "input"))
      (node (ref "IC6") (pin "7") (pinfunction "VSS_7") (pintype "power_in"))
      (node (ref "IC6") (pin "8") (pinfunction "S_8") (pintype "input"))
      (node (ref "IC7") (pin "3") (pinfunction "+IN_3") (pintype "input"))
      (node (ref "IC8") (pin "8") (pinfunction "VSS_8") (pintype "power_in"))
      (node (ref "IC9") (pin "12") (pinfunction "GND_12") (pintype "power_in"))
      (node (ref "IR1") (pin "2") (pinfunction "GND_2") (pintype "power_in"))
      (node (ref "Q3") (pin "E") (pinfunction "E_E") (pintype "passive"))
      (node (ref "Q5") (pin "E") (pinfunction "E_E") (pintype "passive"))
      (node (ref "Q6") (pin "E") (pinfunction "E_E") (pintype "passive"))
      (node (ref "R21") (pin "2") (pinfunction "2_2") (pintype "passive"))
      (node (ref "R22") (pin "2") (pinfunction "2_2") (pintype "passive"))
      (node (ref "R28") (pin "1") (pinfunction "1_1") (pintype "passive"))
      (node (ref "R31") (pin "1") (pinfunction "1_1") (pintype "passive"))
      (node (ref "R41") (pin "1") (pinfunction "1_1") (pintype "passive"))
      (node (ref "R45") (pin "1") (pinfunction "1_1") (pintype "passive"))
      (node (ref "R46") (pin "1") (pinfunction "1_1") (pintype "passive"))
      (node (ref "R47") (pin "1") (pinfunction "1_1") (pintype "passive"))
      (node (ref "R48") (pin "1") (pinfunction "1_1") (pintype "passive"))
      (node (ref "R49") (pin "2") (pinfunction "2_2") (pintype "passive"))
      (node (ref "T3") (pin "E") (pinfunction "E_E") (pintype "passive"))
      (node (ref "T4") (pin "E") (pinfunction "E_E") (pintype "passive"))
      (node (ref "TR1") (pin "13") (pinfunction "5_13") (pintype "passive"))
      (node (ref "TR1") (pin "9") (pinfunction "4_9") (pintype "passive"))
    )
    (net (code "7") (name "Net-(C4-Pad+)") (class "Default")
      (node (ref "C4") (pin "+") (pinfunction "+_+") (pintype "passive"))
      (node (ref "C6") (pin "+") (pinfunction "+_+") (pintype "passive"))
      (node (ref "D10") (pin "C") (pinfunction "C_C") (pintype "passive"))
      (node (ref "D11") (pin "C") (pinfunction "C_C") (pintype "passive"))
      (node (ref "IC12") (pin "IN") (pinfunction "IN_IN") (pintype "input"))
    )
    (net (code "8") (name "Net-(C5-Pad+)") (class "Default")
      (node (ref "C5") (pin "+") (pinfunction "+_+") (pintype "passive"))
      (node (ref "D12") (pin "A") (pinfunction "A_A") (pintype "passive"))
      (node (ref "D13") (pin "A") (pinfunction "A_A") (pintype "passive"))
      (node (ref "R23") (pin "2") (pinfunction "2_2") (pintype "passive"))
    )
    (net (code "9") (name "Net-(C22-Pad2)") (class "Default")
      (node (ref "C22") (pin "2") (pinfunction "2_2") (pintype "passive"))
      (node (ref "D16") (pin "C") (pinfunction "C_C") (pintype "passive"))
      (node (ref "D19") (pin "A") (pinfunction "A_A") (pintype "passive"))
      (node (ref "D20") (pin "A") (pinfunction "A_A") (pintype "passive"))
      (node (ref "D21") (pin "A") (pinfunction "A_A") (pintype "passive"))
      (node (ref "D22") (pin "A") (pinfunction "A_A") (pintype "passive"))
      (node (ref "R28") (pin "2") (pinfunction "2_2") (pintype "passive"))
      (node (ref "R34") (pin "2") (pinfunction "2_2") (pintype "passive"))
    )
    (net (code "10") (name "Net-(C25-Pad1)") (class "Default")
      (node (ref "C25") (pin "1") (pinfunction "1_1") (pintype "passive"))
      (node (ref "R56") (pin "2") (pinfunction "2_2") (pintype "passive"))
      (node (ref "R57") (pin "1") (pinfunction "1_1") (pintype "passive"))
    )
    (net (code "11") (name "Net-(C26-Pad1)") (class "Default")
      (node (ref "C26") (pin "1") (pinfunction "1_1") (pintype "passive"))
      (node (ref "R58") (pin "1") (pinfunction "1_1") (pintype "passive"))
    )
    (net (code "12") (name "Net-(C27-Pad1)") (class "Default")
      (node (ref "C27") (pin "1") (pinfunction "1_1") (pintype "passive"))
      (node (ref "R59") (pin "2") (pinfunction "2_2") (pintype "passive"))
      (node (ref "R60") (pin "1") (pinfunction "1_1") (pintype "passive"))
    )
    (net (code "13") (name "Net-(C28-Pad1)") (class "Default")
      (node (ref "C28") (pin "1") (pinfunction "1_1") (pintype "passive"))
      (node (ref "R61") (pin "1") (pinfunction "1_1") (pintype "passive"))
    )
    (net (code "14") (name "Net-(D9-PadA)") (class "Default")
      (node (ref "D9") (pin "A") (pinfunction "A_A") (pintype "passive"))
      (node (ref "R18") (pin "1") (pinfunction "1_1") (pintype "passive"))
      (node (ref "R19") (pin "2") (pinfunction "2_2") (pintype "passive"))
    )
    (net (code "15") (name "Net-(D18-PadA)") (class "Default")
      (node (ref "D18") (pin "A") (pinfunction "A_A") (pintype "passive"))
      (node (ref "R31") (pin "2") (pinfunction "2_2") (pintype "passive"))
      (node (ref "R32") (pin "2") (pinfunction "2_2") (pintype "passive"))
    )
    (net (code "16") (name "Net-(D18-PadC)") (class "Default")
      (node (ref "D18") (pin "C") (pinfunction "C_C") (pintype "passive"))
      (node (ref "Q2") (pin "C") (pinfunction "C_C") (pintype "passive"))
      (node (ref "R30") (pin "2") (pinfunction "2_2") (pintype "passive"))
    )
    (net (code "17") (name "Net-(IC1-CV)") (class "Default")
      (node (ref "C1") (pin "1") (pinfunction "1_1") (pintype "passive"))
      (node (ref "IC1") (pin "5") (pinfunction "CV_5") (pintype "input"))
    )
    (net (code "18") (name "Net-(IC1-DIS)") (class "Default")
      (node (ref "C2") (pin "1") (pinfunction "1_1") (pintype "passive"))
      (node (ref "IC1") (pin "6") (pinfunction "THR_6") (pintype "input"))
      (node (ref "IC1") (pin "7") (pinfunction "DIS_7") (pintype "input"))
      (node (ref "R3") (pin "1") (pinfunction "1_1") (pintype "passive"))
    )
    (net (code "19") (name "Net-(IC1-Q)") (class "Default")
      (node (ref "D1") (pin "A") (pinfunction "A_A") (pintype "passive"))
      (node (ref "IC1") (pin "3") (pinfunction "Q_3") (pintype "output"))
    )
    (net (code "20") (name "Net-(IC1-TR)") (class "Default")
      (node (ref "C3") (pin "1") (pinfunction "1_1") (pintype "passive"))
      (node (ref "D2") (pin "A") (pinfunction "A_A") (pintype "passive"))
      (node (ref "IC1") (pin "2") (pinfunction "TR_2") (pintype "input"))
      (node (ref "R2") (pin "1") (pinfunction "1_1") (pintype "passive"))
    )
    (net (code "21") (name "Net-(IC2-CV)") (class "Default")
      (node (ref "C7") (pin "1") (pinfunction "1_1") (pintype "passive"))
      (node (ref "IC2") (pin "5") (pinfunction "CV_5") (pintype "input"))
    )
    (net (code "22") (name "Net-(IC2-DIS)") (class "Default")
      (node (ref "C8") (pin "1") (pinfunction "1_1") (pintype "passive"))
      (node (ref "IC2") (pin "6") (pinfunction "THR_6") (pintype "input"))
      (node (ref "IC2") (pin "7") (pinfunction "DIS_7") (pintype "input"))
      (node (ref "R6") (pin "1") (pinfunction "1_1") (pintype "passive"))
    )
    (net (code "23") (name "Net-(IC2-Q)") (class "Default")
      (node (ref "D3") (pin "A") (pinfunction "A_A") (pintype "passive"))
      (node (ref "IC2") (pin "3") (pinfunction "Q_3") (pintype "output"))
    )
    (net (code "24") (name "Net-(IC2-TR)") (class "Default")
      (node (ref "C9") (pin "1") (pinfunction "1_1") (pintype "passive"))
      (node (ref "D4") (pin "A") (pinfunction "A_A") (pintype "passive"))
      (node (ref "IC2") (pin "2") (pinfunction "TR_2") (pintype "input"))
      (node (ref "R5") (pin "1") (pinfunction "1_1") (pintype "passive"))
    )
    (net (code "25") (name "Net-(IC3-CV)") (class "Default")
      (node (ref "C10") (pin "1") (pinfunction "1_1") (pintype "passive"))
      (node (ref "IC3") (pin "5") (pinfunction "CV_5") (pintype "input"))
    )
    (net (code "26") (name "Net-(IC3-DIS)") (class "Default")
      (node (ref "C11") (pin "1") (pinfunction "1_1") (pintype "passive"))
      (node (ref "IC3") (pin "6") (pinfunction "THR_6") (pintype "input"))
      (node (ref "IC3") (pin "7") (pinfunction "DIS_7") (pintype "input"))
      (node (ref "R9") (pin "1") (pinfunction "1_1") (pintype "passive"))
    )
    (net (code "27") (name "Net-(IC3-Q)") (class "Default")
      (node (ref "D5") (pin "A") (pinfunction "A_A") (pintype "passive"))
      (node (ref "IC3") (pin "3") (pinfunction "Q_3") (pintype "output"))
    )
    (net (code "28") (name "Net-(IC3-TR)") (class "Default")
      (node (ref "C12") (pin "1") (pinfunction "1_1") (pintype "passive"))
      (node (ref "D6") (pin "A") (pinfunction "A_A") (pintype "passive"))
      (node (ref "IC3") (pin "2") (pinfunction "TR_2") (pintype "input"))
      (node (ref "R8") (pin "1") (pinfunction "1_1") (pintype "passive"))
    )
    (net (code "29") (name "Net-(IC4-CV)") (class "Default")
      (node (ref "C13") (pin "1") (pinfunction "1_1") (pintype "passive"))
      (node (ref "IC4") (pin "5") (pinfunction "CV_5") (pintype "input"))
    )
    (net (code "30") (name "Net-(IC4-DIS)") (class "Default")
      (node (ref "C14") (pin "1") (pinfunction "1_1") (pintype "passive"))
      (node (ref "IC4") (pin "6") (pinfunction "THR_6") (pintype "input"))
      (node (ref "IC4") (pin "7") (pinfunction "DIS_7") (pintype "input"))
      (node (ref "R12") (pin "1") (pinfunction "1_1") (pintype "passive"))
    )
    (net (code "31") (name "Net-(IC4-Q)") (class "Default")
      (node (ref "D7") (pin "A") (pinfunction "A_A") (pintype "passive"))
      (node (ref "IC4") (pin "3") (pinfunction "Q_3") (pintype "output"))
    )
    (net (code "32") (name "Net-(IC4-TR)") (class "Default")
      (node (ref "C15") (pin "1") (pinfunction "1_1") (pintype "passive"))
      (node (ref "D8") (pin "A") (pinfunction "A_A") (pintype "passive"))
      (node (ref "IC4") (pin "2") (pinfunction "TR_2") (pintype "input"))
      (node (ref "R11") (pin "1") (pinfunction "1_1") (pintype "passive"))
    )
    (net (code "33") (name "Net-(IC5-CV)") (class "Default")
      (node (ref "C16") (pin "1") (pinfunction "1_1") (pintype "passive"))
      (node (ref "IC5") (pin "5") (pinfunction "CV_5") (pintype "input"))
    )
    (net (code "34") (name "Net-(IC5-DIS)") (class "Default")
      (node (ref "IC5") (pin "7") (pinfunction "DIS_7") (pintype "input"))
      (node (ref "R16") (pin "1") (pinfunction "1_1") (pintype "passive"))
      (node (ref "R17") (pin "E") (pinfunction "E_E") (pintype "passive"))
      (node (ref "R17") (pin "S") (pinfunction "S_S") (pintype "passive"))
    )
    (net (code "35") (name "Net-(IC5-Q)") (class "Default")
      (node (ref "IC5") (pin "3") (pinfunction "Q_3") (pintype "output"))
      (node (ref "R13") (pin "1") (pinfunction "1_1") (pintype "passive"))
    )
    (net (code "36") (name "Net-(IC5-R)") (class "Default")
      (node (ref "D1") (pin "C") (pinfunction "C_C") (pintype "passive"))
      (node (ref "D3") (pin "C") (pinfunction "C_C") (pintype "passive"))
      (node (ref "D5") (pin "C") (pinfunction "C_C") (pintype "passive"))
      (node (ref "D7") (pin "C") (pinfunction "C_C") (pintype "passive"))
      (node (ref "IC5") (pin "4") (pinfunction "R_4") (pintype "input"))
      (node (ref "R20") (pin "2") (pinfunction "2_2") (pintype "passive"))
    )
    (net (code "37") (name "Net-(IC5-THR)") (class "Default")
      (node (ref "C17") (pin "1") (pinfunction "1_1") (pintype "passive"))
      (node (ref "IC5") (pin "2") (pinfunction "TR_2") (pintype "input"))
      (node (ref "IC5") (pin "6") (pinfunction "THR_6") (pintype "input"))
      (node (ref "R15") (pin "1") (pinfunction "1_1") (pintype "passive"))
    )
    (net (code "38") (name "Net-(IC6A-CLK)") (class "Default")
      (node (ref "IC6") (pin "3") (pinfunction "CLK_3") (pintype "input"))
      (node (ref "IC9") (pin "2") (pinfunction "OUT_2") (pintype "open_collector"))
      (node (ref "R37") (pin "1") (pinfunction "1_1") (pintype "passive"))
    )
    (net (code "39") (name "Net-(IC6A-R)") (class "Default")
      (node (ref "D19") (pin "C") (pinfunction "C_C") (pintype "passive"))
      (node (ref "IC6") (pin "4") (pinfunction "R_4") (pintype "input"))
      (node (ref "R45") (pin "2") (pinfunction "2_2") (pintype "passive"))
    )
    (net (code "40") (name "Net-(IC6B-CLK)") (class "Default")
      (node (ref "IC6") (pin "11") (pinfunction "CLK_11") (pintype "input"))
      (node (ref "IC9") (pin "1") (pinfunction "OUT_1") (pintype "open_collector"))
      (node (ref "R42") (pin "1") (pinfunction "1_1") (pintype "passive"))
    )
    (net (code "41") (name "Net-(IC6B-R)") (class "Default")
      (node (ref "D20") (pin "C") (pinfunction "C_C") (pintype "passive"))
      (node (ref "D23") (pin "C") (pinfunction "C_C") (pintype "passive"))
      (node (ref "IC6") (pin "10") (pinfunction "R_10") (pintype "input"))
      (node (ref "R46") (pin "2") (pinfunction "2_2") (pintype "passive"))
    )
    (net (code "42") (name "Net-(IC7--IN)") (class "Default")
      (node (ref "C23") (pin "1") (pinfunction "1_1") (pintype "passive"))
      (node (ref "IC7") (pin "2") (pinfunction "-IN_2") (pintype "input"))
      (node (ref "Q4") (pin "E") (pinfunction "E_E") (pintype "passive"))
      (node (ref "R32") (pin "1") (pinfunction "1_1") (pintype "passive"))
      (node (ref "R33") (pin "1") (pinfunction "1_1") (pintype "passive"))
    )
    (net (code "43") (name "Net-(IC7-OUT)") (class "Default")
      (node (ref "C23") (pin "2") (pinfunction "2_2") (pintype "passive"))
      (node (ref "IC7") (pin "6") (pinfunction "OUT_6") (pintype "output"))
      (node (ref "IC9") (pin "11") (pinfunction "+IN_11") (pintype "input"))
      (node (ref "IC9") (pin "5") (pinfunction "+IN_5") (pintype "input"))
      (node (ref "IC9") (pin "7") (pinfunction "+IN_7") (pintype "input"))
      (node (ref "IC9") (pin "9") (pinfunction "+IN_9") (pintype "input"))
      (node (ref "Q4") (pin "C") (pinfunction "C_C") (pintype "passive"))
      (node (ref "R33") (pin "2") (pinfunction "2_2") (pintype "passive"))
    )
    (net (code "44") (name "Net-(IC8A-A)") (class "Default")
      (node (ref "C22") (pin "1") (pinfunction "1_1") (pintype "passive"))
      (node (ref "IC8") (pin "4") (pinfunction "A_4") (pintype "input"))
      (node (ref "Q3") (pin "C") (pinfunction "C_C") (pintype "passive"))
      (node (ref "R26") (pin "1") (pinfunction "1_1") (pintype "passive"))
      (node (ref "R29") (pin "1") (pinfunction "1_1") (pintype "passive"))
    )
    (net (code "45") (name "Net-(IC8A-T1)") (class "Default")
      (node (ref "C24") (pin "-") (pinfunction "-_-") (pintype "passive"))
      (node (ref "IC8") (pin "1") (pinfunction "T1_1") (pintype "input"))
    )
    (net (code "46") (name "Net-(IC8A-T2)") (class "Default")
      (node (ref "C24") (pin "+") (pinfunction "+_+") (pintype "passive"))
      (node (ref "IC8") (pin "2") (pinfunction "T2_2") (pintype "input"))
      (node (ref "R35") (pin "1") (pinfunction "1_1") (pintype "passive"))
    )
    (net (code "47") (name "Net-(IC9A--IN)") (class "Default")
      (node (ref "IC9") (pin "4") (pinfunction "-IN_4") (pintype "input"))
      (node (ref "R36") (pin "1") (pinfunction "1_1") (pintype "passive"))
      (node (ref "R38") (pin "2") (pinfunction "2_2") (pintype "passive"))
    )
    (net (code "48") (name "Net-(IC9B--IN)") (class "Default")
      (node (ref "IC9") (pin "6") (pinfunction "-IN_6") (pintype "input"))
      (node (ref "R38") (pin "1") (pinfunction "1_1") (pintype "passive"))
      (node (ref "R39") (pin "2") (pinfunction "2_2") (pintype "passive"))
    )
    (net (code "49") (name "Net-(IC9C--IN)") (class "Default")
      (node (ref "IC9") (pin "8") (pinfunction "-IN_8") (pintype "input"))
      (node (ref "R39") (pin "1") (pinfunction "1_1") (pintype "passive"))
      (node (ref "R40") (pin "2") (pinfunction "2_2") (pintype "passive"))
    )
    (net (code "50") (name "Net-(IC9D--IN)") (class "Default")
      (node (ref "IC9") (pin "10") (pinfunction "-IN_10") (pintype "input"))
      (node (ref "R40") (pin "1") (pinfunction "1_1") (pintype "passive"))
      (node (ref "R41") (pin "2") (pinfunction "2_2") (pintype "passive"))
    )
    (net (code "51") (name "Net-(IC10A-CLK)") (class "Default")
      (node (ref "IC10") (pin "3") (pinfunction "CLK_3") (pintype "input"))
      (node (ref "IC9") (pin "14") (pinfunction "OUT_14") (pintype "open_collector"))
      (node (ref "R43") (pin "1") (pinfunction "1_1") (pintype "passive"))
    )
    (net (code "52") (name "Net-(IC10A-Q)") (class "Default")
      (node (ref "D25") (pin "A") (pinfunction "A_A") (pintype "passive"))
      (node (ref "IC10") (pin "1") (pinfunction "Q_1") (pintype "output"))
      (node (ref "IC13") (pin "5") (pinfunction "K_5") (pintype "input"))
      (node (ref "IC13") (pin "6") (pinfunction "J_6") (pintype "input"))
    )
    (net (code "53") (name "Net-(IC10A-R)") (class "Default")
      (node (ref "D21") (pin "C") (pinfunction "C_C") (pintype "passive"))
      (node (ref "D24") (pin "C") (pinfunction "C_C") (pintype "passive"))
      (node (ref "IC10") (pin "4") (pinfunction "R_4") (pintype "input"))
      (node (ref "R47") (pin "2") (pinfunction "2_2") (pintype "passive"))
    )
    (net (code "54") (name "Net-(IC10B-CLK)") (class "Default")
      (node (ref "IC10") (pin "11") (pinfunction "CLK_11") (pintype "input"))
      (node (ref "IC9") (pin "13") (pinfunction "OUT_13") (pintype "open_collector"))
      (node (ref "R44") (pin "1") (pinfunction "1_1") (pintype "passive"))
    )
    (net (code "55") (name "Net-(IC10B-Q)") (class "Default")
      (node (ref "IC10") (pin "13") (pinfunction "Q_13") (pintype "output"))
      (node (ref "IC13") (pin "10") (pinfunction "J_10") (pintype "input"))
      (node (ref "IC13") (pin "11") (pinfunction "K_11") (pintype "input"))
    )
    (net (code "56") (name "Net-(IC10B-R)") (class "Default")
      (node (ref "D22") (pin "C") (pinfunction "C_C") (pintype "passive"))
      (node (ref "D25") (pin "C") (pinfunction "C_C") (pintype "passive"))
      (node (ref "IC10") (pin "10") (pinfunction "R_10") (pintype "input"))
      (node (ref "R48") (pin "2") (pinfunction "2_2") (pintype "passive"))
    )
    (net (code "57") (name "Net-(IC11A-CLK)") (class "Default")
      (node (ref "IC11") (pin "13") (pinfunction "CLK_13") (pintype "input"))
      (node (ref "IC11") (pin "3") (pinfunction "CLK_3") (pintype "input"))
      (node (ref "IC13") (pin "13") (pinfunction "CLK_13") (pintype "input"))
      (node (ref "IC13") (pin "3") (pinfunction "CLK_3") (pintype "input"))
      (node (ref "IC8") (pin "7") (pinfunction "~{Q}_7") (pintype "output"))
    )
    (net (code "58") (name "Net-(IC11A-J)") (class "Default")
      (node (ref "D23") (pin "A") (pinfunction "A_A") (pintype "passive"))
      (node (ref "IC11") (pin "5") (pinfunction "K_5") (pintype "input"))
      (node (ref "IC11") (pin "6") (pinfunction "J_6") (pintype "input"))
      (node (ref "IC6") (pin "1") (pinfunction "Q_1") (pintype "output"))
    )
    (net (code "59") (name "Net-(IC11A-Q)") (class "Default")
      (node (ref "IC11") (pin "1") (pinfunction "Q_1") (pintype "output"))
      (node (ref "R52") (pin "1") (pinfunction "1_1") (pintype "passive"))
    )
    (net (code "60") (name "Net-(IC11A-R)") (class "Default")
      (node (ref "C21") (pin "-") (pinfunction "-_-") (pintype "passive"))
      (node (ref "IC11") (pin "12") (pinfunction "R_12") (pintype "input"))
      (node (ref "IC11") (pin "4") (pinfunction "R_4") (pintype "input"))
      (node (ref "IC13") (pin "12") (pinfunction "R_12") (pintype "input"))
      (node (ref "IC13") (pin "4") (pinfunction "R_4") (pintype "input"))
      (node (ref "R49") (pin "1") (pinfunction "1_1") (pintype "passive"))
    )
    (net (code "61") (name "Net-(IC11B-J)") (class "Default")
      (node (ref "D24") (pin "A") (pinfunction "A_A") (pintype "passive"))
      (node (ref "IC11") (pin "10") (pinfunction "J_10") (pintype "input"))
      (node (ref "IC11") (pin "11") (pinfunction "K_11") (pintype "input"))
      (node (ref "IC6") (pin "13") (pinfunction "Q_13") (pintype "output"))
    )
    (net (code "62") (name "Net-(IC11B-Q)") (class "Default")
      (node (ref "IC11") (pin "15") (pinfunction "Q_15") (pintype "output"))
      (node (ref "R55") (pin "1") (pinfunction "1_1") (pintype "passive"))
    )
    (net (code "63") (name "Net-(IC13A-Q)") (class "Default")
      (node (ref "IC13") (pin "1") (pinfunction "Q_1") (pintype "output"))
      (node (ref "R64") (pin "2") (pinfunction "2_2") (pintype "passive"))
    )
    (net (code "64") (name "Net-(IC13B-Q)") (class "Default")
      (node (ref "IC13") (pin "15") (pinfunction "Q_15") (pintype "output"))
      (node (ref "R62") (pin "2") (pinfunction "2_2") (pintype "passive"))
    )
    (net (code "65") (name "Net-(IR1-OUT)") (class "Default")
      (node (ref "IR1") (pin "1") (pinfunction "OUT_1") (pintype "output"))
      (node (ref "R24") (pin "1") (pinfunction "1_1") (pintype "passive"))
      (node (ref "R27") (pin "2") (pinfunction "2_2") (pintype "passive"))
    )
    (net (code "66") (name "Net-(K1A--)") (class "Default")
      (node (ref "D27") (pin "A") (pinfunction "A_A") (pintype "passive"))
      (node (ref "K1") (pin "12") (pinfunction "-_12") (pintype "passive"))
      (node (ref "R65") (pin "2") (pinfunction "2_2") (pintype "passive"))
      (node (ref "T4") (pin "C") (pinfunction "C_C") (pintype "passive"))
    )
    (net (code "67") (name "Net-(K1B-O)") (class "Default")
      (node (ref "K1") (pin "1") (pinfunction "O_1") (pintype "passive"))
      (node (ref "X4") (pin "2") (pinfunction "KL_2") (pintype "passive"))
    )
    (net (code "68") (name "Net-(K1B-P)") (class "Default")
      (node (ref "K1") (pin "7") (pinfunction "P_7") (pintype "passive"))
      (node (ref "X4") (pin "1") (pinfunction "KL_1") (pintype "passive"))
    )
    (net (code "69") (name "Net-(K2A--)") (class "Default")
      (node (ref "D26") (pin "A") (pinfunction "A_A") (pintype "passive"))
      (node (ref "K2") (pin "12") (pinfunction "-_12") (pintype "passive"))
      (node (ref "R63") (pin "2") (pinfunction "2_2") (pintype "passive"))
      (node (ref "T3") (pin "C") (pinfunction "C_C") (pintype "passive"))
    )
    (net (code "70") (name "Net-(K2B-O)") (class "Default")
      (node (ref "K2") (pin "1") (pinfunction "O_1") (pintype "passive"))
      (node (ref "X5") (pin "2") (pinfunction "KL_2") (pintype "passive"))
    )
    (net (code "71") (name "Net-(K2B-P)") (class "Default")
      (node (ref "K2") (pin "7") (pinfunction "P_7") (pintype "passive"))
      (node (ref "X5") (pin "1") (pinfunction "KL_1") (pintype "passive"))
    )
    (net (code "72") (name "Net-(LED1-PadA)") (class "Default")
      (node (ref "LED1") (pin "A") (pinfunction "A_A") (pintype "passive"))
      (node (ref "R19") (pin "1") (pinfunction "1_1") (pintype "passive"))
    )
    (net (code "73") (name "Net-(LED2-C)") (class "Default")
      (node (ref "LED2") (pin "K") (pinfunction "C_K") (pintype "passive"))
      (node (ref "R22") (pin "1") (pinfunction "1_1") (pintype "passive"))
    )
    (net (code "74") (name "Net-(LED3-PadA)") (class "Default")
      (node (ref "LED3") (pin "A") (pinfunction "A_A") (pintype "passive"))
      (node (ref "R21") (pin "1") (pinfunction "1_1") (pintype "passive"))
    )
    (net (code "75") (name "Net-(LED4-C)") (class "Default")
      (node (ref "LED4") (pin "K") (pinfunction "C_K") (pintype "passive"))
      (node (ref "R51") (pin "1") (pinfunction "1_1") (pintype "passive"))
    )
    (net (code "76") (name "Net-(LED5-C)") (class "Default")
      (node (ref "LED5") (pin "K") (pinfunction "C_K") (pintype "passive"))
      (node (ref "R54") (pin "1") (pinfunction "1_1") (pintype "passive"))
    )
    (net (code "77") (name "Net-(LED6-C)") (class "Default")
      (node (ref "LED6") (pin "K") (pinfunction "C_K") (pintype "passive"))
      (node (ref "R63") (pin "1") (pinfunction "1_1") (pintype "passive"))
    )
    (net (code "78") (name "Net-(LED7-C)") (class "Default")
      (node (ref "LED7") (pin "K") (pinfunction "C_K") (pintype "passive"))
      (node (ref "R65") (pin "1") (pinfunction "1_1") (pintype "passive"))
    )
    (net (code "79") (name "Net-(OK1-A)") (class "Default")
      (node (ref "OK1") (pin "1") (pinfunction "A_1") (pintype "passive"))
      (node (ref "R50") (pin "2") (pinfunction "2_2") (pintype "passive"))
    )
    (net (code "80") (name "Net-(OK1-A1)") (class "Default")
      (node (ref "OK1") (pin "4") (pinfunction "A1_4") (pintype "passive"))
      (node (ref "T1") (pin "G") (pinfunction "G_G") (pintype "passive"))
    )
    (net (code "81") (name "Net-(OK1-A2)") (class "Default")
      (node (ref "OK1") (pin "6") (pinfunction "A2_6") (pintype "passive"))
      (node (ref "R56") (pin "1") (pinfunction "1_1") (pintype "passive"))
    )
    (net (code "82") (name "Net-(OK1-C)") (class "Default")
      (node (ref "OK1") (pin "2") (pinfunction "C_2") (pintype "passive"))
      (node (ref "Q5") (pin "C") (pinfunction "C_C") (pintype "passive"))
      (node (ref "R51") (pin "2") (pinfunction "2_2") (pintype "passive"))
    )
    (net (code "83") (name "Net-(OK2-A)") (class "Default")
      (node (ref "OK2") (pin "1") (pinfunction "A_1") (pintype "passive"))
      (node (ref "R53") (pin "2") (pinfunction "2_2") (pintype "passive"))
    )
    (net (code "84") (name "Net-(OK2-A1)") (class "Default")
      (node (ref "OK2") (pin "4") (pinfunction "A1_4") (pintype "passive"))
      (node (ref "T2") (pin "G") (pinfunction "G_G") (pintype "passive"))
    )
    (net (code "85") (name "Net-(OK2-A2)") (class "Default")
      (node (ref "OK2") (pin "6") (pinfunction "A2_6") (pintype "passive"))
      (node (ref "R59") (pin "1") (pinfunction "1_1") (pintype "passive"))
    )
    (net (code "86") (name "Net-(OK2-C)") (class "Default")
      (node (ref "OK2") (pin "2") (pinfunction "C_2") (pintype "passive"))
      (node (ref "Q6") (pin "C") (pinfunction "C_C") (pintype "passive"))
      (node (ref "R54") (pin "2") (pinfunction "2_2") (pintype "passive"))
    )
    (net (code "87") (name "Net-(Q1-B)") (class "Default")
      (node (ref "Q1") (pin "2") (pinfunction "B_2") (pintype "passive"))
      (node (ref "R13") (pin "2") (pinfunction "2_2") (pintype "passive"))
      (node (ref "R14") (pin "1") (pinfunction "1_1") (pintype "passive"))
    )
    (net (code "88") (name "Net-(Q1-C)") (class "Default")
      (node (ref "Q1") (pin "3") (pinfunction "C_3") (pintype "passive"))
      (node (ref "R18") (pin "2") (pinfunction "2_2") (pintype "passive"))
    )
    (net (code "89") (name "Net-(Q2-PadB)") (class "Default")
      (node (ref "Q2") (pin "B") (pinfunction "B_B") (pintype "passive"))
      (node (ref "R29") (pin "2") (pinfunction "2_2") (pintype "passive"))
    )
    (net (code "90") (name "Net-(Q3-PadB)") (class "Default")
      (node (ref "Q3") (pin "B") (pinfunction "B_B") (pintype "passive"))
      (node (ref "R27") (pin "1") (pinfunction "1_1") (pintype "passive"))
    )
    (net (code "91") (name "Net-(Q4-PadB)") (class "Default")
      (node (ref "Q4") (pin "B") (pinfunction "B_B") (pintype "passive"))
      (node (ref "R34") (pin "1") (pinfunction "1_1") (pintype "passive"))
    )
    (net (code "92") (name "Net-(Q5-PadB)") (class "Default")
      (node (ref "Q5") (pin "B") (pinfunction "B_B") (pintype "passive"))
      (node (ref "R52") (pin "2") (pinfunction "2_2") (pintype "passive"))
    )
    (net (code "93") (name "Net-(Q6-PadB)") (class "Default")
      (node (ref "Q6") (pin "B") (pinfunction "B_B") (pintype "passive"))
      (node (ref "R55") (pin "2") (pinfunction "2_2") (pintype "passive"))
    )
    (net (code "94") (name "Net-(R15-Pad2)") (class "Default")
      (node (ref "R15") (pin "2") (pinfunction "2_2") (pintype "passive"))
      (node (ref "R17") (pin "A") (pinfunction "A_A") (pintype "passive"))
    )
    (net (code "95") (name "Net-(R62-Pad1)") (class "Default")
      (node (ref "R62") (pin "1") (pinfunction "1_1") (pintype "passive"))
      (node (ref "T3") (pin "B") (pinfunction "B_B") (pintype "passive"))
    )
    (net (code "96") (name "Net-(R64-Pad1)") (class "Default")
      (node (ref "R64") (pin "1") (pinfunction "1_1") (pintype "passive"))
      (node (ref "T4") (pin "B") (pinfunction "B_B") (pintype "passive"))
    )
    (net (code "97") (name "Net-(S1-S)") (class "Default")
      (node (ref "C3") (pin "2") (pinfunction "2_2") (pintype "passive"))
      (node (ref "R1") (pin "1") (pinfunction "1_1") (pintype "passive"))
      (node (ref "S1") (pin "1") (pinfunction "S_1") (pintype "passive"))
      (node (ref "S1") (pin "2") (pinfunction "S1_2") (pintype "passive"))
    )
    (net (code "98") (name "Net-(S2-S)") (class "Default")
      (node (ref "C9") (pin "2") (pinfunction "2_2") (pintype "passive"))
      (node (ref "R4") (pin "1") (pinfunction "1_1") (pintype "passive"))
      (node (ref "S2") (pin "1") (pinfunction "S_1") (pintype "passive"))
      (node (ref "S2") (pin "2") (pinfunction "S1_2") (pintype "passive"))
    )
    (net (code "99") (name "Net-(S3-S)") (class "Default")
      (node (ref "C12") (pin "2") (pinfunction "2_2") (pintype "passive"))
      (node (ref "R7") (pin "1") (pinfunction "1_1") (pintype "passive"))
      (node (ref "S3") (pin "1") (pinfunction "S_1") (pintype "passive"))
      (node (ref "S3") (pin "2") (pinfunction "S1_2") (pintype "passive"))
    )
    (net (code "100") (name "Net-(S4-S)") (class "Default")
      (node (ref "C15") (pin "2") (pinfunction "2_2") (pintype "passive"))
      (node (ref "R10") (pin "1") (pinfunction "1_1") (pintype "passive"))
      (node (ref "S4") (pin "1") (pinfunction "S_1") (pintype "passive"))
      (node (ref "S4") (pin "2") (pinfunction "S1_2") (pintype "passive"))
    )
    (net (code "101") (name "Net-(T1-A1)") (class "Default")
      (node (ref "C25") (pin "2") (pinfunction "2_2") (pintype "passive"))
      (node (ref "C26") (pin "2") (pinfunction "2_2") (pintype "passive"))
      (node (ref "T1") (pin "T1") (pinfunction "A1_T1") (pintype "passive"))
      (node (ref "X2") (pin "1") (pinfunction "KL_1") (pintype "passive"))
    )
    (net (code "102") (name "Net-(T1-A2)") (class "Default")
      (node (ref "R57") (pin "2") (pinfunction "2_2") (pintype "passive"))
      (node (ref "R58") (pin "2") (pinfunction "2_2") (pintype "passive"))
      (node (ref "R60") (pin "2") (pinfunction "2_2") (pintype "passive"))
      (node (ref "R61") (pin "2") (pinfunction "2_2") (pintype "passive"))
      (node (ref "T1") (pin "T2") (pinfunction "A2_T2") (pintype "passive"))
      (node (ref "T2") (pin "T2") (pinfunction "A2_T2") (pintype "passive"))
      (node (ref "TR1") (pin "7") (pinfunction "2_7") (pintype "passive"))
      (node (ref "X1") (pin "1") (pinfunction "KL_1") (pintype "passive"))
    )
    (net (code "103") (name "Net-(T2-A1)") (class "Default")
      (node (ref "C27") (pin "2") (pinfunction "2_2") (pintype "passive"))
      (node (ref "C28") (pin "2") (pinfunction "2_2") (pintype "passive"))
      (node (ref "T2") (pin "T1") (pinfunction "A1_T1") (pintype "passive"))
      (node (ref "X3") (pin "1") (pinfunction "KL_1") (pintype "passive"))
    )
    (net (code "104") (name "Net-(TR1-3)") (class "Default")
      (node (ref "D11") (pin "A") (pinfunction "A_A") (pintype "passive"))
      (node (ref "D13") (pin "C") (pinfunction "C_C") (pintype "passive"))
      (node (ref "TR1") (pin "8") (pinfunction "3_8") (pintype "passive"))
    )
    (net (code "105") (name "Net-(TR1-6)") (class "Default")
      (node (ref "D10") (pin "A") (pinfunction "A_A") (pintype "passive"))
      (node (ref "D12") (pin "C") (pinfunction "C_C") (pintype "passive"))
      (node (ref "TR1") (pin "14") (pinfunction "6_14") (pintype "passive"))
    )
    (net (code "106") (name "Net-(X1B-KL)") (class "Default")
      (node (ref "F1") (pin "2") (pinfunction "2_2") (pintype "passive"))
      (node (ref "TR1") (pin "1") (pinfunction "1_1") (pintype "passive"))
      (node (ref "X1") (pin "2") (pinfunction "KL_2") (pintype "passive"))
    )
    (net (code "107") (name "Net-(X2B-KL)") (class "Default")
      (node (ref "F1") (pin "1") (pinfunction "1_1") (pintype "passive"))
      (node (ref "X2") (pin "2") (pinfunction "KL_2") (pintype "passive"))
      (node (ref "X3") (pin "2") (pinfunction "KL_2") (pintype "passive"))
    )
    (net (code "108") (name "unconnected-(IC6A-~{Q}-Pad2)") (class "Default")
      (node (ref "IC6") (pin "2") (pinfunction "~{Q}_2") (pintype "output"))
    )
    (net (code "109") (name "unconnected-(IC6B-~{Q}-Pad12)") (class "Default")
      (node (ref "IC6") (pin "12") (pinfunction "~{Q}_12") (pintype "output"))
    )
    (net (code "110") (name "unconnected-(IC7-ON1-Pad1)") (class "Default")
      (node (ref "IC7") (pin "1") (pinfunction "ON1_1") (pintype "passive"))
    )
    (net (code "111") (name "unconnected-(IC7-ON2-Pad5)") (class "Default")
      (node (ref "IC7") (pin "5") (pinfunction "ON2_5") (pintype "passive"))
    )
    (net (code "112") (name "unconnected-(IC7-OPT-Pad8)") (class "Default")
      (node (ref "IC7") (pin "8") (pinfunction "OPT_8") (pintype "passive"))
    )
    (net (code "113") (name "unconnected-(IC8A-Q-Pad6)") (class "Default")
      (node (ref "IC8") (pin "6") (pinfunction "Q_6") (pintype "output"))
    )
    (net (code "114") (name "unconnected-(IC10A-~{Q}-Pad2)") (class "Default")
      (node (ref "IC10") (pin "2") (pinfunction "~{Q}_2") (pintype "output"))
    )
    (net (code "115") (name "unconnected-(IC10B-~{Q}-Pad12)") (class "Default")
      (node (ref "IC10") (pin "12") (pinfunction "~{Q}_12") (pintype "output"))
    )
    (net (code "116") (name "unconnected-(IC11A-~{Q}-Pad2)") (class "Default")
      (node (ref "IC11") (pin "2") (pinfunction "~{Q}_2") (pintype "output"))
    )
    (net (code "117") (name "unconnected-(IC11B-~{Q}-Pad14)") (class "Default")
      (node (ref "IC11") (pin "14") (pinfunction "~{Q}_14") (pintype "output"))
    )
    (net (code "118") (name "unconnected-(IC13A-~{Q}-Pad2)") (class "Default")
      (node (ref "IC13") (pin "2") (pinfunction "~{Q}_2") (pintype "output"))
    )
    (net (code "119") (name "unconnected-(IC13B-~{Q}-Pad14)") (class "Default")
      (node (ref "IC13") (pin "14") (pinfunction "~{Q}_14") (pintype "output"))
    )
    (net (code "120") (name "unconnected-(K1B-S-Pad2)") (class "Default")
      (node (ref "K1") (pin "2") (pinfunction "S_2") (pintype "passive"))
    )
    (net (code "121") (name "unconnected-(K2B-S-Pad2)") (class "Default")
      (node (ref "K2") (pin "2") (pinfunction "S_2") (pintype "passive"))
    )
  )
)
